# SCH_Just-random_2026-04-02.net
KiCad netlist of a schematic drawn in EasyEDA
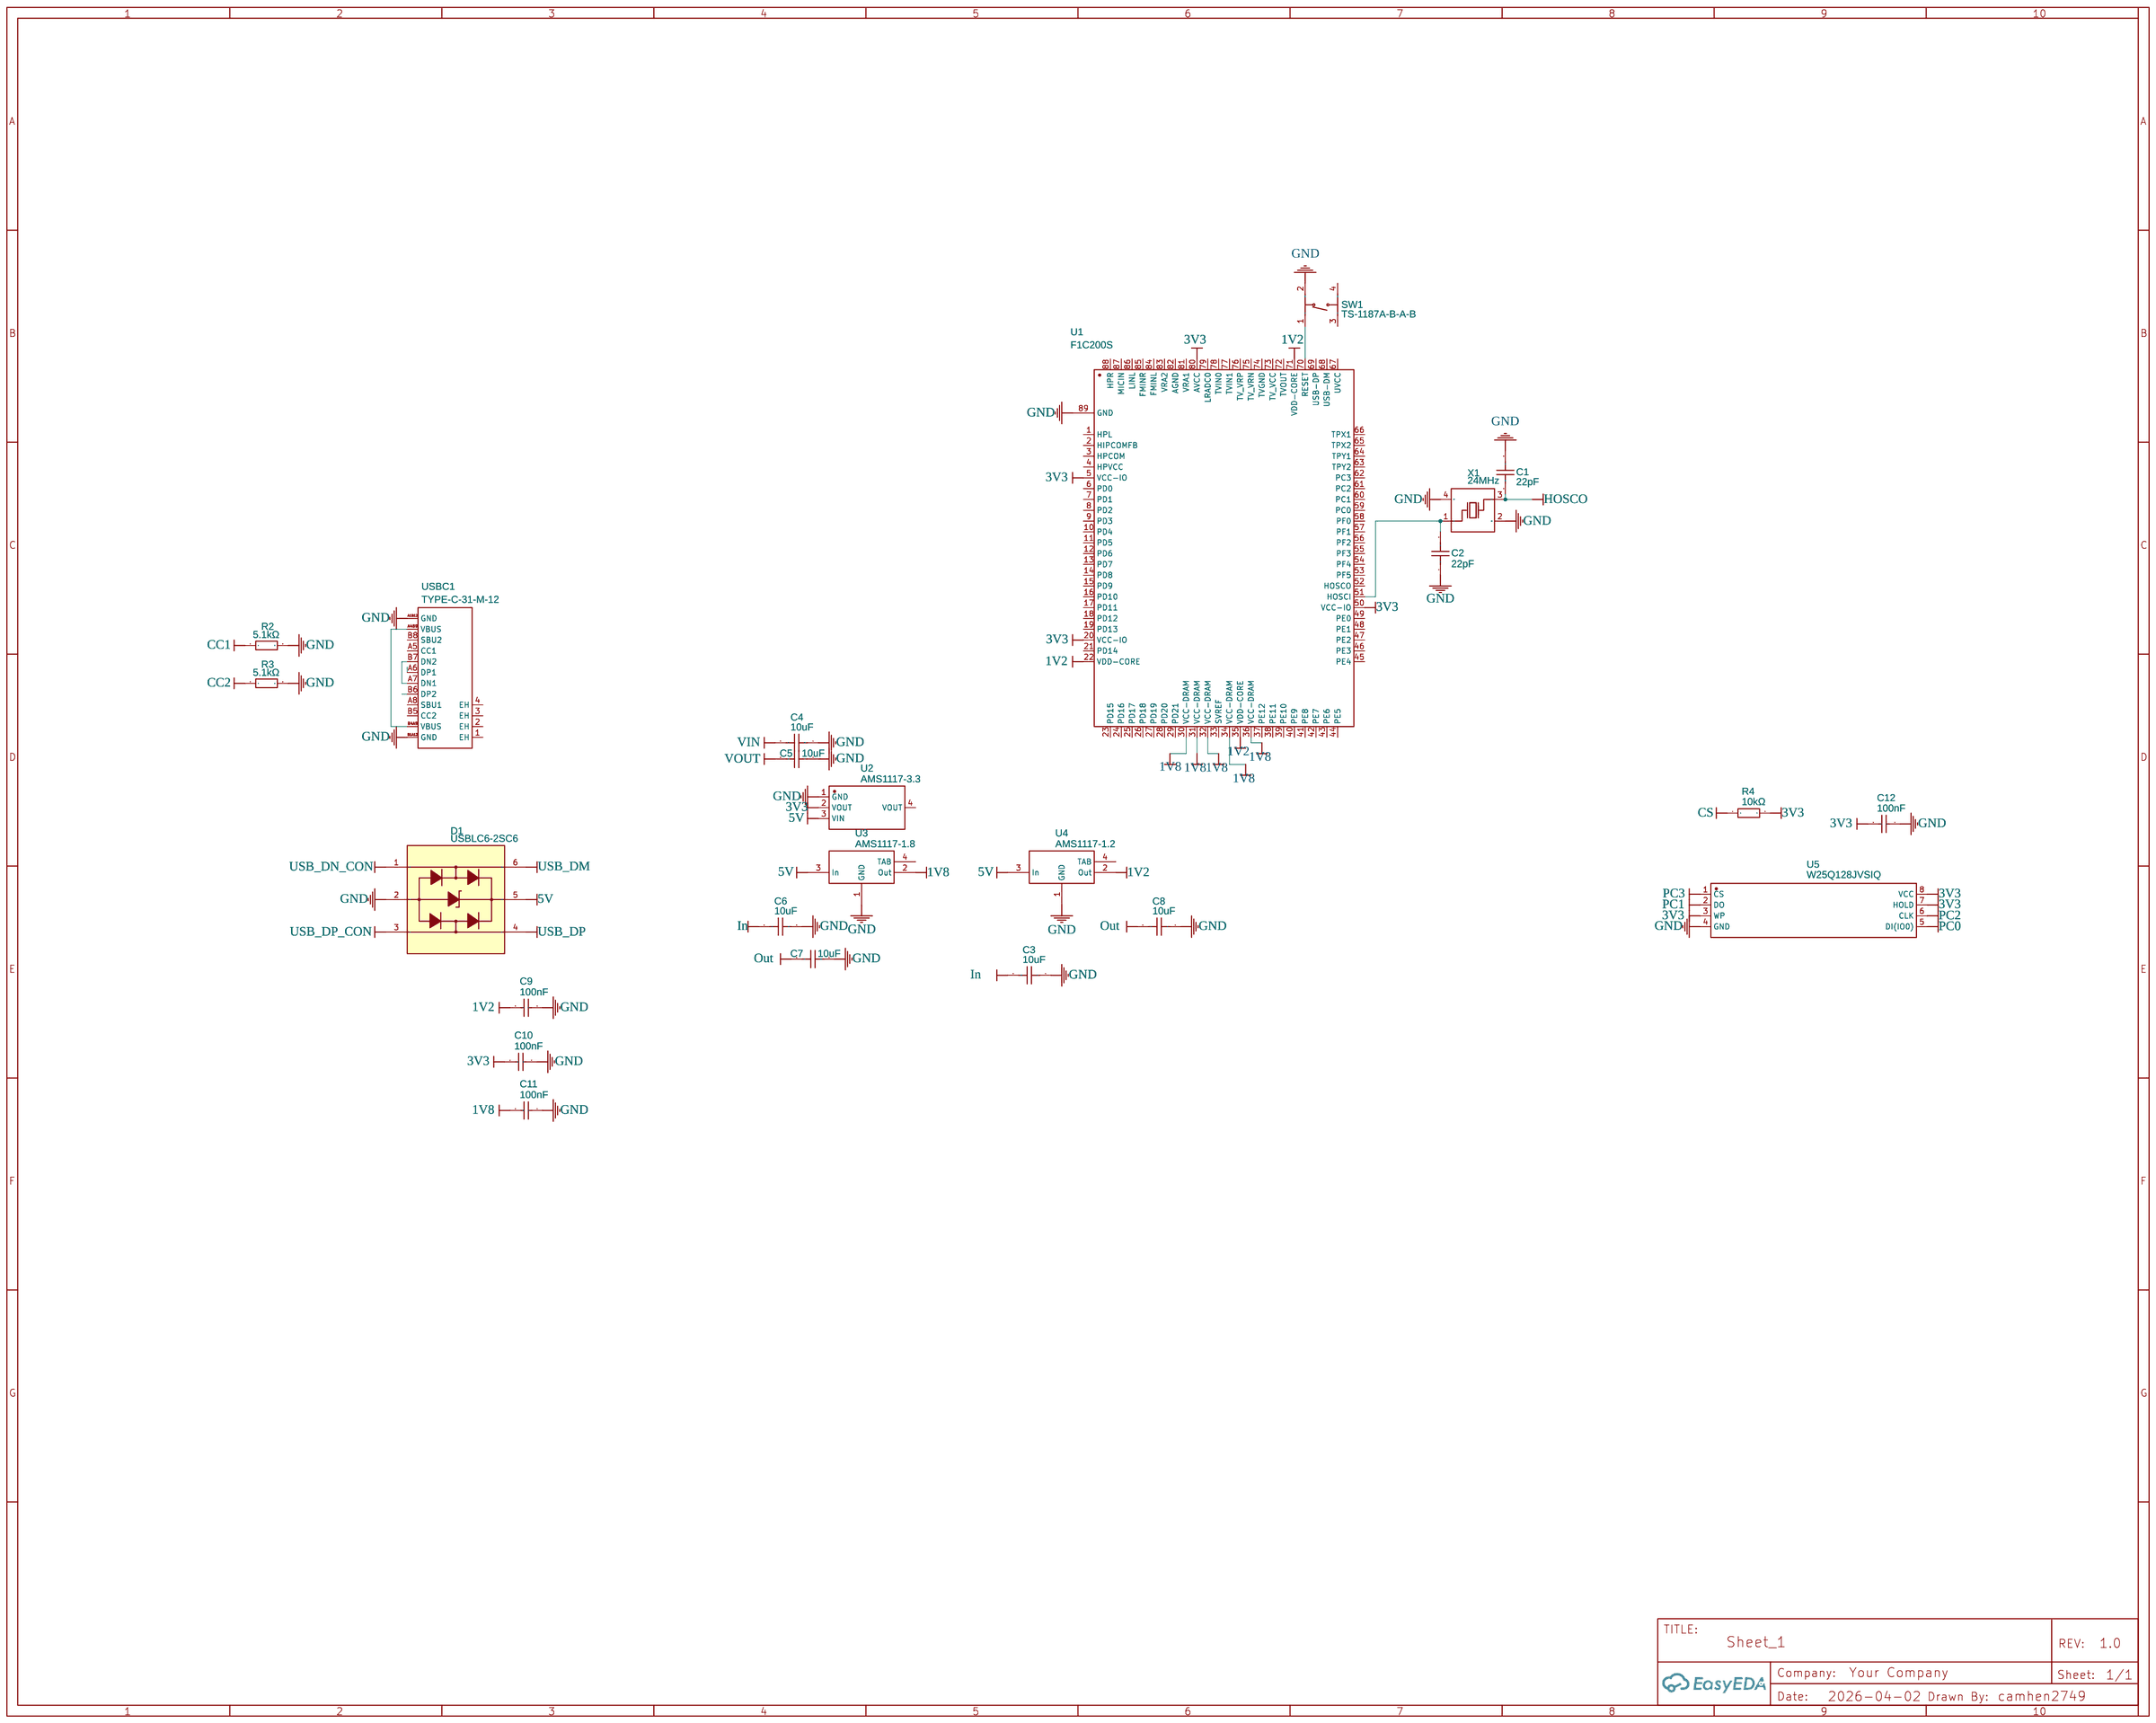
[diagram p0: schematic sheet]

(export (version "E")
  (design (tool "Eeschema 10.0.6"))
  (components
    (comp (ref "C1")
      (value "22pF")
      (fields (field (name "Manufacturer Part") "C1608CH2A220J080AA") (field (name "Manufacturer") "TDK"))
      (libsource (lib "") (part "C1608CH2A220J080AA"))
    )
    (comp (ref "C2")
      (value "22pF")
      (fields (field (name "Manufacturer Part") "C1608CH2A220J080AA") (field (name "Manufacturer") "TDK"))
      (libsource (lib "") (part "C1608CH2A220J080AA"))
    )
    (comp (ref "C3")
      (value "10uF")
      (fields
        (field (name "Manufacturer Part") "CC0603KRX5R6BB106")
        (field (name "Manufacturer") "YAGEO(国巨)")
      )
      (libsource (lib "") (part "CC0603KRX5R6BB106"))
    )
    (comp (ref "C4")
      (value "10uF")
      (fields
        (field (name "Manufacturer Part") "CC0603KRX5R6BB106")
        (field (name "Manufacturer") "YAGEO(国巨)")
      )
      (libsource (lib "") (part "CC0603KRX5R6BB106"))
    )
    (comp (ref "C5")
      (value "10uF")
      (fields
        (field (name "Manufacturer Part") "CC0603KRX5R6BB106")
        (field (name "Manufacturer") "YAGEO(国巨)")
      )
      (libsource (lib "") (part "CC0603KRX5R6BB106"))
    )
    (comp (ref "C6")
      (value "10uF")
      (fields
        (field (name "Manufacturer Part") "CC0603KRX5R6BB106")
        (field (name "Manufacturer") "YAGEO(国巨)")
      )
      (libsource (lib "") (part "CC0603KRX5R6BB106"))
    )
    (comp (ref "C7")
      (value "10uF")
      (fields
        (field (name "Manufacturer Part") "CC0603KRX5R6BB106")
        (field (name "Manufacturer") "YAGEO(国巨)")
      )
      (libsource (lib "") (part "CC0603KRX5R6BB106"))
    )
    (comp (ref "C8")
      (value "10uF")
      (fields
        (field (name "Manufacturer Part") "CC0603KRX5R6BB106")
        (field (name "Manufacturer") "YAGEO(国巨)")
      )
      (libsource (lib "") (part "CC0603KRX5R6BB106"))
    )
    (comp (ref "C9")
      (value "100nF")
      (fields
        (field (name "Manufacturer Part") "CC0402KRX7R9BB104")
        (field (name "Manufacturer") "YAGEO(国巨)")
      )
      (libsource (lib "") (part "CC0402KRX7R9BB104"))
    )
    (comp (ref "C10")
      (value "100nF")
      (fields
        (field (name "Manufacturer Part") "CC0402KRX7R9BB104")
        (field (name "Manufacturer") "YAGEO(国巨)")
      )
      (libsource (lib "") (part "CC0402KRX7R9BB104"))
    )
    (comp (ref "C11")
      (value "100nF")
      (fields
        (field (name "Manufacturer Part") "CC0402KRX7R9BB104")
        (field (name "Manufacturer") "YAGEO(国巨)")
      )
      (libsource (lib "") (part "CC0402KRX7R9BB104"))
    )
    (comp (ref "C12")
      (value "100nF")
      (fields
        (field (name "Manufacturer Part") "CC0402KRX7R9BB104")
        (field (name "Manufacturer") "YAGEO(国巨)")
      )
      (libsource (lib "") (part "CC0402KRX7R9BB104"))
    )
    (comp (ref "D1")
      (value "USBLC6-2SC6")
      (fields (field (name "Manufacturer") "ST(意法半导体)"))
      (libsource (lib "") (part "USBLC6-2SC6"))
    )
    (comp (ref "R2")
      (value "5.1kΩ")
      (fields (field (name "Manufacturer Part") "RC0402FR-075K1L") (field (name "Manufacturer") "YAGEO(国巨)"))
      (libsource (lib "") (part "RC0402FR-075K1L"))
    )
    (comp (ref "R3")
      (value "5.1kΩ")
      (fields (field (name "Manufacturer Part") "RC0402FR-075K1L") (field (name "Manufacturer") "YAGEO(国巨)"))
      (libsource (lib "") (part "RC0402FR-075K1L"))
    )
    (comp (ref "R4")
      (value "10kΩ")
      (fields (field (name "Manufacturer Part") "RC0402FR-0710KL") (field (name "Manufacturer") "YAGEO(国巨)"))
      (libsource (lib "") (part "RC0402FR-0710KL"))
    )
    (comp (ref "SW1")
      (value "TS-1187A-B-A-B")
      (fields (field (name "Manufacturer") "XKB Connection(中国星坤)"))
      (libsource (lib "") (part "TS-1187A-B-A-B"))
    )
    (comp (ref "U1")
      (value "F1C200S")
      (fields (field (name "Manufacturer") "Allwinner(全志)"))
      (libsource (lib "") (part "F1C200S"))
    )
    (comp (ref "U2")
      (value "AMS1117-3.3")
      (fields (field (name "Manufacturer") "AMS"))
      (libsource (lib "") (part "AMS1117-3.3"))
    )
    (comp (ref "U3")
      (value "AMS1117-1.8")
      (fields (field (name "Manufacturer") "AMS"))
      (libsource (lib "") (part "AMS1117-1.8"))
    )
    (comp (ref "U4")
      (value "AMS1117-1.2")
      (fields (field (name "Manufacturer") "AMS"))
      (libsource (lib "") (part "AMS1117-1.2"))
    )
    (comp (ref "U5")
      (value "W25Q128JVSIQ")
      (fields (field (name "Manufacturer") "Winbond(华邦)"))
      (libsource (lib "") (part "W25Q128JVSIQ"))
    )
    (comp (ref "USBC1")
      (value "TYPE-C-31-M-12")
      (fields (field (name "Manufacturer") "韩国韩荣"))
      (libsource (lib "") (part "TYPE-C-31-M-12"))
    )
    (comp (ref "X1")
      (value "24MHz")
      (fields (field (name "Manufacturer Part") "X322524MSB4SI") (field (name "Manufacturer") "YXC(扬兴晶振)"))
      (libsource (lib "") (part "X322524MSB4SI"))
    )
  )
  (nets
    (net (code "1") (name "1V2") (class "Default")
      (node (ref "C9") (pin "1") (pinfunction "1_1") (pintype "input"))
      (node (ref "U1") (pin "22") (pinfunction "VDD-CORE_22") (pintype "unspecified"))
      (node (ref "U1") (pin "35") (pinfunction "VDD-CORE_35") (pintype "unspecified"))
      (node (ref "U1") (pin "71") (pinfunction "VDD-CORE_71") (pintype "unspecified"))
      (node (ref "U4") (pin "2") (pinfunction "Out_2") (pintype "unspecified"))
    )
    (net (code "2") (name "1V8") (class "Default")
      (node (ref "C11") (pin "1") (pinfunction "1_1") (pintype "input"))
      (node (ref "U1") (pin "30") (pinfunction "VCC-DRAM_30") (pintype "unspecified"))
      (node (ref "U1") (pin "31") (pinfunction "VCC-DRAM_31") (pintype "unspecified"))
      (node (ref "U1") (pin "32") (pinfunction "VCC-DRAM_32") (pintype "unspecified"))
      (node (ref "U1") (pin "34") (pinfunction "VCC-DRAM_34") (pintype "unspecified"))
      (node (ref "U1") (pin "36") (pinfunction "VCC-DRAM_36") (pintype "unspecified"))
      (node (ref "U3") (pin "2") (pinfunction "Out_2") (pintype "unspecified"))
    )
    (net (code "3") (name "3V3") (class "Default")
      (node (ref "C10") (pin "1") (pinfunction "1_1") (pintype "input"))
      (node (ref "C12") (pin "1") (pinfunction "1_1") (pintype "input"))
      (node (ref "R4") (pin "2") (pinfunction "2_2") (pintype "input"))
      (node (ref "U1") (pin "20") (pinfunction "VCC-IO_20") (pintype "unspecified"))
      (node (ref "U1") (pin "5") (pinfunction "VCC-IO_5") (pintype "unspecified"))
      (node (ref "U1") (pin "50") (pinfunction "VCC-IO_50") (pintype "unspecified"))
      (node (ref "U1") (pin "80") (pinfunction "AVCC_80") (pintype "unspecified"))
      (node (ref "U2") (pin "2") (pinfunction "VOUT_2") (pintype "unspecified"))
      (node (ref "U5") (pin "3") (pinfunction "WP_3") (pintype "unspecified"))
      (node (ref "U5") (pin "7") (pinfunction "HOLD_7") (pintype "unspecified"))
      (node (ref "U5") (pin "8") (pinfunction "VCC_8") (pintype "unspecified"))
    )
    (net (code "4") (name "5V") (class "Default")
      (node (ref "D1") (pin "5") (pinfunction "5_5") (pintype "input"))
      (node (ref "U2") (pin "3") (pinfunction "VIN_3") (pintype "unspecified"))
      (node (ref "U3") (pin "3") (pinfunction "In_3") (pintype "unspecified"))
      (node (ref "U4") (pin "3") (pinfunction "In_3") (pintype "unspecified"))
    )
    (net (code "5") (name "CC1") (class "Default")
      (node (ref "R2") (pin "1") (pinfunction "1_1") (pintype "input"))
    )
    (net (code "6") (name "CC2") (class "Default")
      (node (ref "R3") (pin "1") (pinfunction "1_1") (pintype "input"))
    )
    (net (code "7") (name "CS") (class "Default")
      (node (ref "R4") (pin "1") (pinfunction "1_1") (pintype "input"))
    )
    (net (code "8") (name "GND") (class "Default")
      (node (ref "C1") (pin "2") (pinfunction "2_2") (pintype "unspecified"))
      (node (ref "C10") (pin "2") (pinfunction "2_2") (pintype "input"))
      (node (ref "C11") (pin "2") (pinfunction "2_2") (pintype "input"))
      (node (ref "C12") (pin "2") (pinfunction "2_2") (pintype "input"))
      (node (ref "C2") (pin "1") (pinfunction "1_1") (pintype "unspecified"))
      (node (ref "C3") (pin "1") (pinfunction "1_1") (pintype "unspecified"))
      (node (ref "C4") (pin "1") (pinfunction "1_1") (pintype "unspecified"))
      (node (ref "C5") (pin "1") (pinfunction "1_1") (pintype "unspecified"))
      (node (ref "C6") (pin "1") (pinfunction "1_1") (pintype "unspecified"))
      (node (ref "C7") (pin "1") (pinfunction "1_1") (pintype "unspecified"))
      (node (ref "C8") (pin "1") (pinfunction "1_1") (pintype "unspecified"))
      (node (ref "C9") (pin "2") (pinfunction "2_2") (pintype "input"))
      (node (ref "D1") (pin "2") (pinfunction "2_2") (pintype "input"))
      (node (ref "R2") (pin "2") (pinfunction "2_2") (pintype "input"))
      (node (ref "R3") (pin "2") (pinfunction "2_2") (pintype "input"))
      (node (ref "SW1") (pin "2") (pinfunction "B_2") (pintype "unspecified"))
      (node (ref "U1") (pin "89") (pinfunction "GND_89") (pintype "unspecified"))
      (node (ref "U2") (pin "1") (pinfunction "GND_1") (pintype "unspecified"))
      (node (ref "U3") (pin "1") (pinfunction "GND_1") (pintype "unspecified"))
      (node (ref "U4") (pin "1") (pinfunction "GND_1") (pintype "unspecified"))
      (node (ref "U5") (pin "4") (pinfunction "GND_4") (pintype "unspecified"))
      (node (ref "USBC1") (pin "A1B12") (pinfunction "GND_A1B12") (pintype "unspecified"))
      (node (ref "USBC1") (pin "B1A12") (pinfunction "GND_B1A12") (pintype "unspecified"))
      (node (ref "X1") (pin "2") (pinfunction "GND_2") (pintype "unspecified"))
      (node (ref "X1") (pin "4") (pinfunction "GND_4") (pintype "unspecified"))
    )
    (net (code "9") (name "HOSCO") (class "Default")
      (node (ref "C1") (pin "1") (pinfunction "1_1") (pintype "unspecified"))
      (node (ref "X1") (pin "3") (pinfunction "OSC2_3") (pintype "unspecified"))
    )
    (net (code "10") (name "In") (class "Default")
      (node (ref "C3") (pin "2") (pinfunction "2_2") (pintype "unspecified"))
      (node (ref "C6") (pin "2") (pinfunction "2_2") (pintype "unspecified"))
    )
    (net (code "11") (name "Net-(SW1-A)") (class "Default")
      (node (ref "SW1") (pin "1") (pinfunction "A_1") (pintype "unspecified"))
      (node (ref "U1") (pin "70") (pinfunction "RESET_70") (pintype "unspecified"))
    )
    (net (code "12") (name "Net-(U1-HOSCI)") (class "Default")
      (node (ref "C2") (pin "2") (pinfunction "2_2") (pintype "unspecified"))
      (node (ref "U1") (pin "51") (pinfunction "HOSCI_51") (pintype "unspecified"))
      (node (ref "X1") (pin "1") (pinfunction "OSC1_1") (pintype "unspecified"))
    )
    (net (code "13") (name "Net-(USBC1-DN1)") (class "Default")
      (node (ref "USBC1") (pin "A7") (pinfunction "DN1_A7") (pintype "unspecified"))
      (node (ref "USBC1") (pin "B7") (pinfunction "DN2_B7") (pintype "unspecified"))
    )
    (net (code "14") (name "Net-(USBC1-VBUS-PadA4B9)") (class "Default")
      (node (ref "USBC1") (pin "A4B9") (pinfunction "VBUS_A4B9") (pintype "unspecified"))
      (node (ref "USBC1") (pin "B4A9") (pinfunction "VBUS_B4A9") (pintype "unspecified"))
    )
    (net (code "15") (name "Out") (class "Default")
      (node (ref "C7") (pin "2") (pinfunction "2_2") (pintype "unspecified"))
      (node (ref "C8") (pin "2") (pinfunction "2_2") (pintype "unspecified"))
    )
    (net (code "16") (name "PC0") (class "Default")
      (node (ref "U5") (pin "5") (pinfunction "DI(IO0)_5") (pintype "unspecified"))
    )
    (net (code "17") (name "PC1") (class "Default")
      (node (ref "U5") (pin "2") (pinfunction "DO_2") (pintype "unspecified"))
    )
    (net (code "18") (name "PC2") (class "Default")
      (node (ref "U5") (pin "6") (pinfunction "CLK_6") (pintype "unspecified"))
    )
    (net (code "19") (name "PC3") (class "Default")
      (node (ref "U5") (pin "1") (pinfunction "CS_1") (pintype "unspecified"))
    )
    (net (code "20") (name "USB_DM") (class "Default")
      (node (ref "D1") (pin "6") (pinfunction "6_6") (pintype "input"))
    )
    (net (code "21") (name "USB_DN_CON") (class "Default")
      (node (ref "D1") (pin "1") (pinfunction "1_1") (pintype "input"))
    )
    (net (code "22") (name "USB_DP") (class "Default")
      (node (ref "D1") (pin "4") (pinfunction "4_4") (pintype "input"))
    )
    (net (code "23") (name "USB_DP_CON") (class "Default")
      (node (ref "D1") (pin "3") (pinfunction "3_3") (pintype "input"))
    )
    (net (code "24") (name "VIN") (class "Default")
      (node (ref "C4") (pin "2") (pinfunction "2_2") (pintype "unspecified"))
    )
    (net (code "25") (name "VOUT") (class "Default")
      (node (ref "C5") (pin "2") (pinfunction "2_2") (pintype "unspecified"))
    )
    (net (code "26") (name "unconnected-(SW1-C-Pad3)") (class "Default")
      (node (ref "SW1") (pin "3") (pinfunction "C_3") (pintype "unspecified"))
    )
    (net (code "27") (name "unconnected-(SW1-D-Pad4)") (class "Default")
      (node (ref "SW1") (pin "4") (pinfunction "D_4") (pintype "unspecified"))
    )
    (net (code "28") (name "unconnected-(U1-AGND-Pad82)") (class "Default")
      (node (ref "U1") (pin "82") (pinfunction "AGND_82") (pintype "unspecified"))
    )
    (net (code "29") (name "unconnected-(U1-FMINL-Pad84)") (class "Default")
      (node (ref "U1") (pin "84") (pinfunction "FMINL_84") (pintype "unspecified"))
    )
    (net (code "30") (name "unconnected-(U1-FMINR-Pad85)") (class "Default")
      (node (ref "U1") (pin "85") (pinfunction "FMINR_85") (pintype "unspecified"))
    )
    (net (code "31") (name "unconnected-(U1-HIPCOMFB-Pad2)") (class "Default")
      (node (ref "U1") (pin "2") (pinfunction "HIPCOMFB_2") (pintype "unspecified"))
    )
    (net (code "32") (name "unconnected-(U1-HOSCO-Pad52)") (class "Default")
      (node (ref "U1") (pin "52") (pinfunction "HOSCO_52") (pintype "unspecified"))
    )
    (net (code "33") (name "unconnected-(U1-HPCOM-Pad3)") (class "Default")
      (node (ref "U1") (pin "3") (pinfunction "HPCOM_3") (pintype "unspecified"))
    )
    (net (code "34") (name "unconnected-(U1-HPL-Pad1)") (class "Default")
      (node (ref "U1") (pin "1") (pinfunction "HPL_1") (pintype "unspecified"))
    )
    (net (code "35") (name "unconnected-(U1-HPR-Pad88)") (class "Default")
      (node (ref "U1") (pin "88") (pinfunction "HPR_88") (pintype "unspecified"))
    )
    (net (code "36") (name "unconnected-(U1-HPVCC-Pad4)") (class "Default")
      (node (ref "U1") (pin "4") (pinfunction "HPVCC_4") (pintype "unspecified"))
    )
    (net (code "37") (name "unconnected-(U1-LINL-Pad86)") (class "Default")
      (node (ref "U1") (pin "86") (pinfunction "LINL_86") (pintype "unspecified"))
    )
    (net (code "38") (name "unconnected-(U1-LRADC0-Pad79)") (class "Default")
      (node (ref "U1") (pin "79") (pinfunction "LRADC0_79") (pintype "unspecified"))
    )
    (net (code "39") (name "unconnected-(U1-MICIN-Pad87)") (class "Default")
      (node (ref "U1") (pin "87") (pinfunction "MICIN_87") (pintype "unspecified"))
    )
    (net (code "40") (name "unconnected-(U1-PC0-Pad59)") (class "Default")
      (node (ref "U1") (pin "59") (pinfunction "PC0_59") (pintype "unspecified"))
    )
    (net (code "41") (name "unconnected-(U1-PC1-Pad60)") (class "Default")
      (node (ref "U1") (pin "60") (pinfunction "PC1_60") (pintype "unspecified"))
    )
    (net (code "42") (name "unconnected-(U1-PC2-Pad61)") (class "Default")
      (node (ref "U1") (pin "61") (pinfunction "PC2_61") (pintype "unspecified"))
    )
    (net (code "43") (name "unconnected-(U1-PC3-Pad62)") (class "Default")
      (node (ref "U1") (pin "62") (pinfunction "PC3_62") (pintype "unspecified"))
    )
    (net (code "44") (name "unconnected-(U1-PD0-Pad6)") (class "Default")
      (node (ref "U1") (pin "6") (pinfunction "PD0_6") (pintype "unspecified"))
    )
    (net (code "45") (name "unconnected-(U1-PD1-Pad7)") (class "Default")
      (node (ref "U1") (pin "7") (pinfunction "PD1_7") (pintype "unspecified"))
    )
    (net (code "46") (name "unconnected-(U1-PD2-Pad8)") (class "Default")
      (node (ref "U1") (pin "8") (pinfunction "PD2_8") (pintype "unspecified"))
    )
    (net (code "47") (name "unconnected-(U1-PD3-Pad9)") (class "Default")
      (node (ref "U1") (pin "9") (pinfunction "PD3_9") (pintype "unspecified"))
    )
    (net (code "48") (name "unconnected-(U1-PD4-Pad10)") (class "Default")
      (node (ref "U1") (pin "10") (pinfunction "PD4_10") (pintype "unspecified"))
    )
    (net (code "49") (name "unconnected-(U1-PD5-Pad11)") (class "Default")
      (node (ref "U1") (pin "11") (pinfunction "PD5_11") (pintype "unspecified"))
    )
    (net (code "50") (name "unconnected-(U1-PD6-Pad12)") (class "Default")
      (node (ref "U1") (pin "12") (pinfunction "PD6_12") (pintype "unspecified"))
    )
    (net (code "51") (name "unconnected-(U1-PD7-Pad13)") (class "Default")
      (node (ref "U1") (pin "13") (pinfunction "PD7_13") (pintype "unspecified"))
    )
    (net (code "52") (name "unconnected-(U1-PD8-Pad14)") (class "Default")
      (node (ref "U1") (pin "14") (pinfunction "PD8_14") (pintype "unspecified"))
    )
    (net (code "53") (name "unconnected-(U1-PD9-Pad15)") (class "Default")
      (node (ref "U1") (pin "15") (pinfunction "PD9_15") (pintype "unspecified"))
    )
    (net (code "54") (name "unconnected-(U1-PD10-Pad16)") (class "Default")
      (node (ref "U1") (pin "16") (pinfunction "PD10_16") (pintype "unspecified"))
    )
    (net (code "55") (name "unconnected-(U1-PD11-Pad17)") (class "Default")
      (node (ref "U1") (pin "17") (pinfunction "PD11_17") (pintype "unspecified"))
    )
    (net (code "56") (name "unconnected-(U1-PD12-Pad18)") (class "Default")
      (node (ref "U1") (pin "18") (pinfunction "PD12_18") (pintype "unspecified"))
    )
    (net (code "57") (name "unconnected-(U1-PD13-Pad19)") (class "Default")
      (node (ref "U1") (pin "19") (pinfunction "PD13_19") (pintype "unspecified"))
    )
    (net (code "58") (name "unconnected-(U1-PD14-Pad21)") (class "Default")
      (node (ref "U1") (pin "21") (pinfunction "PD14_21") (pintype "unspecified"))
    )
    (net (code "59") (name "unconnected-(U1-PD15-Pad23)") (class "Default")
      (node (ref "U1") (pin "23") (pinfunction "PD15_23") (pintype "unspecified"))
    )
    (net (code "60") (name "unconnected-(U1-PD16-Pad24)") (class "Default")
      (node (ref "U1") (pin "24") (pinfunction "PD16_24") (pintype "unspecified"))
    )
    (net (code "61") (name "unconnected-(U1-PD17-Pad25)") (class "Default")
      (node (ref "U1") (pin "25") (pinfunction "PD17_25") (pintype "unspecified"))
    )
    (net (code "62") (name "unconnected-(U1-PD18-Pad26)") (class "Default")
      (node (ref "U1") (pin "26") (pinfunction "PD18_26") (pintype "unspecified"))
    )
    (net (code "63") (name "unconnected-(U1-PD19-Pad27)") (class "Default")
      (node (ref "U1") (pin "27") (pinfunction "PD19_27") (pintype "unspecified"))
    )
    (net (code "64") (name "unconnected-(U1-PD20-Pad28)") (class "Default")
      (node (ref "U1") (pin "28") (pinfunction "PD20_28") (pintype "unspecified"))
    )
    (net (code "65") (name "unconnected-(U1-PD21-Pad29)") (class "Default")
      (node (ref "U1") (pin "29") (pinfunction "PD21_29") (pintype "unspecified"))
    )
    (net (code "66") (name "unconnected-(U1-PE0-Pad49)") (class "Default")
      (node (ref "U1") (pin "49") (pinfunction "PE0_49") (pintype "unspecified"))
    )
    (net (code "67") (name "unconnected-(U1-PE1-Pad48)") (class "Default")
      (node (ref "U1") (pin "48") (pinfunction "PE1_48") (pintype "unspecified"))
    )
    (net (code "68") (name "unconnected-(U1-PE2-Pad47)") (class "Default")
      (node (ref "U1") (pin "47") (pinfunction "PE2_47") (pintype "unspecified"))
    )
    (net (code "69") (name "unconnected-(U1-PE3-Pad46)") (class "Default")
      (node (ref "U1") (pin "46") (pinfunction "PE3_46") (pintype "unspecified"))
    )
    (net (code "70") (name "unconnected-(U1-PE4-Pad45)") (class "Default")
      (node (ref "U1") (pin "45") (pinfunction "PE4_45") (pintype "unspecified"))
    )
    (net (code "71") (name "unconnected-(U1-PE5-Pad44)") (class "Default")
      (node (ref "U1") (pin "44") (pinfunction "PE5_44") (pintype "unspecified"))
    )
    (net (code "72") (name "unconnected-(U1-PE6-Pad43)") (class "Default")
      (node (ref "U1") (pin "43") (pinfunction "PE6_43") (pintype "unspecified"))
    )
    (net (code "73") (name "unconnected-(U1-PE7-Pad42)") (class "Default")
      (node (ref "U1") (pin "42") (pinfunction "PE7_42") (pintype "unspecified"))
    )
    (net (code "74") (name "unconnected-(U1-PE8-Pad41)") (class "Default")
      (node (ref "U1") (pin "41") (pinfunction "PE8_41") (pintype "unspecified"))
    )
    (net (code "75") (name "unconnected-(U1-PE9-Pad40)") (class "Default")
      (node (ref "U1") (pin "40") (pinfunction "PE9_40") (pintype "unspecified"))
    )
    (net (code "76") (name "unconnected-(U1-PE10-Pad39)") (class "Default")
      (node (ref "U1") (pin "39") (pinfunction "PE10_39") (pintype "unspecified"))
    )
    (net (code "77") (name "unconnected-(U1-PE11-Pad38)") (class "Default")
      (node (ref "U1") (pin "38") (pinfunction "PE11_38") (pintype "unspecified"))
    )
    (net (code "78") (name "unconnected-(U1-PE12-Pad37)") (class "Default")
      (node (ref "U1") (pin "37") (pinfunction "PE12_37") (pintype "unspecified"))
    )
    (net (code "79") (name "unconnected-(U1-PF0-Pad58)") (class "Default")
      (node (ref "U1") (pin "58") (pinfunction "PF0_58") (pintype "unspecified"))
    )
    (net (code "80") (name "unconnected-(U1-PF1-Pad57)") (class "Default")
      (node (ref "U1") (pin "57") (pinfunction "PF1_57") (pintype "unspecified"))
    )
    (net (code "81") (name "unconnected-(U1-PF2-Pad56)") (class "Default")
      (node (ref "U1") (pin "56") (pinfunction "PF2_56") (pintype "unspecified"))
    )
    (net (code "82") (name "unconnected-(U1-PF3-Pad55)") (class "Default")
      (node (ref "U1") (pin "55") (pinfunction "PF3_55") (pintype "unspecified"))
    )
    (net (code "83") (name "unconnected-(U1-PF4-Pad54)") (class "Default")
      (node (ref "U1") (pin "54") (pinfunction "PF4_54") (pintype "unspecified"))
    )
    (net (code "84") (name "unconnected-(U1-PF5-Pad53)") (class "Default")
      (node (ref "U1") (pin "53") (pinfunction "PF5_53") (pintype "unspecified"))
    )
    (net (code "85") (name "unconnected-(U1-SVREF-Pad33)") (class "Default")
      (node (ref "U1") (pin "33") (pinfunction "SVREF_33") (pintype "unspecified"))
    )
    (net (code "86") (name "unconnected-(U1-TPX1-Pad66)") (class "Default")
      (node (ref "U1") (pin "66") (pinfunction "TPX1_66") (pintype "unspecified"))
    )
    (net (code "87") (name "unconnected-(U1-TPX2-Pad65)") (class "Default")
      (node (ref "U1") (pin "65") (pinfunction "TPX2_65") (pintype "unspecified"))
    )
    (net (code "88") (name "unconnected-(U1-TPY1-Pad64)") (class "Default")
      (node (ref "U1") (pin "64") (pinfunction "TPY1_64") (pintype "unspecified"))
    )
    (net (code "89") (name "unconnected-(U1-TPY2-Pad63)") (class "Default")
      (node (ref "U1") (pin "63") (pinfunction "TPY2_63") (pintype "unspecified"))
    )
    (net (code "90") (name "unconnected-(U1-TVGND-Pad74)") (class "Default")
      (node (ref "U1") (pin "74") (pinfunction "TVGND_74") (pintype "unspecified"))
    )
    (net (code "91") (name "unconnected-(U1-TVIN0-Pad78)") (class "Default")
      (node (ref "U1") (pin "78") (pinfunction "TVIN0_78") (pintype "unspecified"))
    )
    (net (code "92") (name "unconnected-(U1-TVIN1-Pad77)") (class "Default")
      (node (ref "U1") (pin "77") (pinfunction "TVIN1_77") (pintype "unspecified"))
    )
    (net (code "93") (name "unconnected-(U1-TVOUT-Pad72)") (class "Default")
      (node (ref "U1") (pin "72") (pinfunction "TVOUT_72") (pintype "unspecified"))
    )
    (net (code "94") (name "unconnected-(U1-TV_VCC-Pad73)") (class "Default")
      (node (ref "U1") (pin "73") (pinfunction "TV_VCC_73") (pintype "unspecified"))
    )
    (net (code "95") (name "unconnected-(U1-TV_VRN-Pad75)") (class "Default")
      (node (ref "U1") (pin "75") (pinfunction "TV_VRN_75") (pintype "unspecified"))
    )
    (net (code "96") (name "unconnected-(U1-TV_VRP-Pad76)") (class "Default")
      (node (ref "U1") (pin "76") (pinfunction "TV_VRP_76") (pintype "unspecified"))
    )
    (net (code "97") (name "unconnected-(U1-USB-DM-Pad68)") (class "Default")
      (node (ref "U1") (pin "68") (pinfunction "USB-DM_68") (pintype "unspecified"))
    )
    (net (code "98") (name "unconnected-(U1-USB-DP-Pad69)") (class "Default")
      (node (ref "U1") (pin "69") (pinfunction "USB-DP_69") (pintype "unspecified"))
    )
    (net (code "99") (name "unconnected-(U1-UVCC-Pad67)") (class "Default")
      (node (ref "U1") (pin "67") (pinfunction "UVCC_67") (pintype "unspecified"))
    )
    (net (code "100") (name "unconnected-(U1-VRA1-Pad81)") (class "Default")
      (node (ref "U1") (pin "81") (pinfunction "VRA1_81") (pintype "unspecified"))
    )
    (net (code "101") (name "unconnected-(U1-VRA2-Pad83)") (class "Default")
      (node (ref "U1") (pin "83") (pinfunction "VRA2_83") (pintype "unspecified"))
    )
    (net (code "102") (name "unconnected-(U2-VOUT-Pad4)") (class "Default")
      (node (ref "U2") (pin "4") (pinfunction "VOUT_4") (pintype "unspecified"))
    )
    (net (code "103") (name "unconnected-(U3-TAB-Pad4)") (class "Default")
      (node (ref "U3") (pin "4") (pinfunction "TAB_4") (pintype "unspecified"))
    )
    (net (code "104") (name "unconnected-(U4-TAB-Pad4)") (class "Default")
      (node (ref "U4") (pin "4") (pinfunction "TAB_4") (pintype "unspecified"))
    )
    (net (code "105") (name "unconnected-(USBC1-CC1-PadA5)") (class "Default")
      (node (ref "USBC1") (pin "A5") (pinfunction "CC1_A5") (pintype "unspecified"))
    )
    (net (code "106") (name "unconnected-(USBC1-CC2-PadB5)") (class "Default")
      (node (ref "USBC1") (pin "B5") (pinfunction "CC2_B5") (pintype "unspecified"))
    )
    (net (code "107") (name "unconnected-(USBC1-DP1-PadA6)") (class "Default")
      (node (ref "USBC1") (pin "A6") (pinfunction "DP1_A6") (pintype "unspecified"))
    )
    (net (code "108") (name "unconnected-(USBC1-DP2-PadB6)") (class "Default")
      (node (ref "USBC1") (pin "B6") (pinfunction "DP2_B6") (pintype "unspecified"))
    )
    (net (code "109") (name "unconnected-(USBC1-EH-Pad1)") (class "Default")
      (node (ref "USBC1") (pin "1") (pinfunction "EH_1") (pintype "unspecified"))
    )
    (net (code "110") (name "unconnected-(USBC1-EH-Pad2)") (class "Default")
      (node (ref "USBC1") (pin "2") (pinfunction "EH_2") (pintype "unspecified"))
    )
    (net (code "111") (name "unconnected-(USBC1-EH-Pad3)") (class "Default")
      (node (ref "USBC1") (pin "3") (pinfunction "EH_3") (pintype "unspecified"))
    )
    (net (code "112") (name "unconnected-(USBC1-EH-Pad4)") (class "Default")
      (node (ref "USBC1") (pin "4") (pinfunction "EH_4") (pintype "unspecified"))
    )
    (net (code "113") (name "unconnected-(USBC1-SBU1-PadA8)") (class "Default")
      (node (ref "USBC1") (pin "A8") (pinfunction "SBU1_A8") (pintype "unspecified"))
    )
    (net (code "114") (name "unconnected-(USBC1-SBU2-PadB8)") (class "Default")
      (node (ref "USBC1") (pin "B8") (pinfunction "SBU2_B8") (pintype "unspecified"))
    )
  )
)
